# Teensy_MouseV2_0_top_Deck.net
KiCad netlist of a schematic drawn in EAGLE
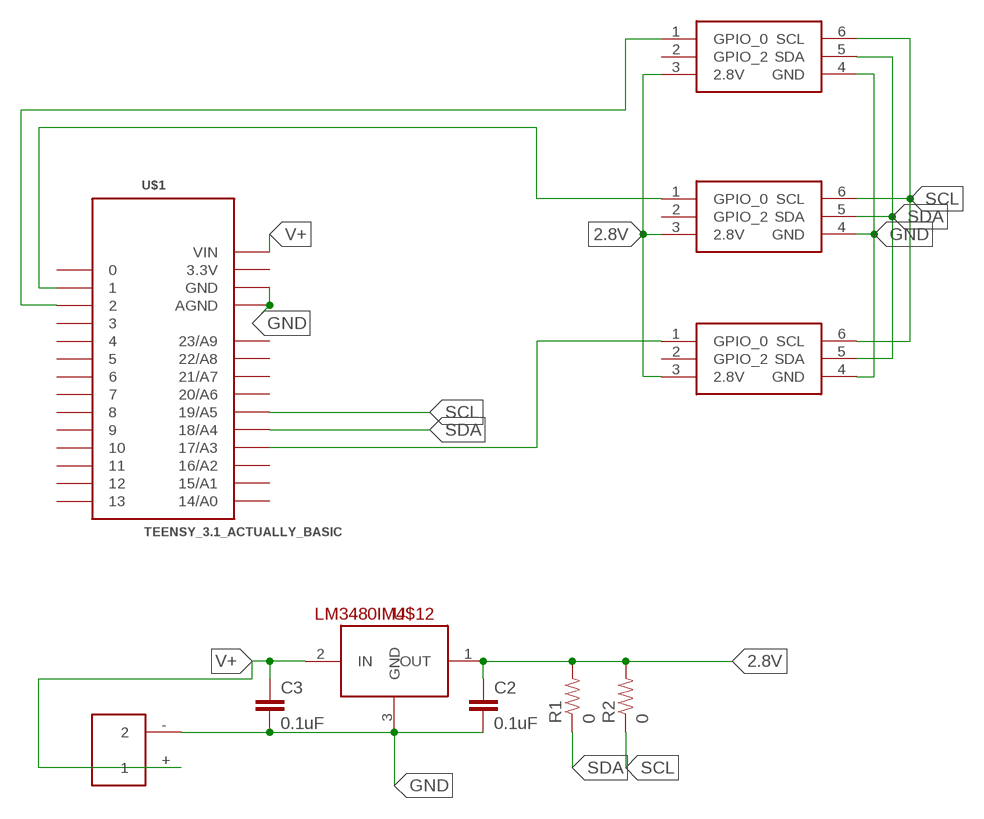
[diagram p0: schematic, sheet 1]

(export (version "E")
  (design (tool "Eeschema 10.0.6"))
  (components
    (comp (ref "C2")
      (value "0.1uF")
      (footprint "eagle-import:0603-CAP")
      (libsource (lib "eagle-import") (part "0.1UF-25V(+80/-20%)(0603)"))
    )
    (comp (ref "C3")
      (value "0.1uF")
      (footprint "eagle-import:0603-CAP")
      (libsource (lib "eagle-import") (part "0.1UF-25V(+80/-20%)(0603)"))
    )
    (comp (ref "R1")
      (value "0")
      (footprint "eagle-import:0603")
      (libsource (lib "eagle-import") (part "0OHM1/10W5%(0603)"))
    )
    (comp (ref "R2")
      (value "0")
      (footprint "eagle-import:0603")
      (libsource (lib "eagle-import") (part "0OHM1/10W5%(0603)"))
    )
    (comp (ref "U$1")
      (value "TEENSY_3.1_ACTUALLY_BASIC")
      (footprint "eagle-import:TEENSY_3.0_ACTUALLY_BASIC")
      (libsource (lib "eagle-import") (part "TEENSY_3.1_ACTUALLY_BASIC"))
    )
    (comp (ref "U$2")
      (value "PICOBLADE2X")
      (footprint "eagle-import:PICOBLADE2X")
      (libsource (lib "eagle-import") (part "PICOBLADE2X"))
    )
    (comp (ref "U$9")
      (value "PATRICK'S_ST_SENSOR_BOARD")
      (footprint "eagle-import:2X3HEADER")
      (libsource (lib "eagle-import") (part "PATRICK'S_ST_SENSOR_BOARD"))
    )
    (comp (ref "U$10")
      (value "PATRICK'S_ST_SENSOR_BOARD")
      (footprint "eagle-import:2X3HEADER")
      (libsource (lib "eagle-import") (part "PATRICK'S_ST_SENSOR_BOARD"))
    )
    (comp (ref "U$11")
      (value "PATRICK'S_ST_SENSOR_BOARD")
      (footprint "eagle-import:2X3HEADER")
      (libsource (lib "eagle-import") (part "PATRICK'S_ST_SENSOR_BOARD"))
    )
    (comp (ref "U$12")
      (value "LM3480IM4")
      (footprint "eagle-import:SOT23-3")
      (libsource (lib "eagle-import") (part "LM3480IM4"))
    )
  )
  (nets
    (net (code "1") (name "/3.3V") (class "Default")
      (node (ref "U$1") (pin "3.3V") (pinfunction "3.3V_3.3V") (pintype "power_in"))
    )
    (net (code "2") (name "2.8V") (class "Default")
      (node (ref "C2") (pin "1") (pinfunction "1_1") (pintype "passive"))
      (node (ref "R1") (pin "2") (pinfunction "2_2") (pintype "passive"))
      (node (ref "R2") (pin "2") (pinfunction "2_2") (pintype "passive"))
      (node (ref "U$10") (pin "3") (pinfunction "2.8V_3") (pintype "bidirectional"))
      (node (ref "U$11") (pin "3") (pinfunction "2.8V_3") (pintype "bidirectional"))
      (node (ref "U$12") (pin "1") (pinfunction "OUT_1") (pintype "bidirectional"))
      (node (ref "U$9") (pin "3") (pinfunction "2.8V_3") (pintype "bidirectional"))
    )
    (net (code "3") (name "GND") (class "Default")
      (node (ref "C2") (pin "2") (pinfunction "2_2") (pintype "passive"))
      (node (ref "C3") (pin "2") (pinfunction "2_2") (pintype "passive"))
      (node (ref "U$1") (pin "AGND") (pinfunction "AGND_AGND") (pintype "power_in"))
      (node (ref "U$1") (pin "GND") (pinfunction "GND_GND") (pintype "power_in"))
      (node (ref "U$10") (pin "4") (pinfunction "GND_4") (pintype "bidirectional"))
      (node (ref "U$11") (pin "4") (pinfunction "GND_4") (pintype "bidirectional"))
      (node (ref "U$12") (pin "3") (pinfunction "GND_3") (pintype "bidirectional"))
      (node (ref "U$2") (pin "-") (pinfunction "2_-") (pintype "bidirectional"))
      (node (ref "U$9") (pin "4") (pinfunction "GND_4") (pintype "bidirectional"))
    )
    (net (code "4") (name "Net-(U$9-GPIO_0)") (class "Default")
      (node (ref "U$1") (pin "2") (pinfunction "2_2") (pintype "bidirectional"))
      (node (ref "U$9") (pin "1") (pinfunction "GPIO_0_1") (pintype "bidirectional"))
    )
    (net (code "5") (name "Net-(U$10-GPIO_0)") (class "Default")
      (node (ref "U$1") (pin "1") (pinfunction "1_1") (pintype "bidirectional"))
      (node (ref "U$10") (pin "1") (pinfunction "GPIO_0_1") (pintype "bidirectional"))
    )
    (net (code "6") (name "Net-(U$11-GPIO_0)") (class "Default")
      (node (ref "U$1") (pin "17/A3") (pinfunction "17/A3_17/A3") (pintype "bidirectional"))
      (node (ref "U$11") (pin "1") (pinfunction "GPIO_0_1") (pintype "bidirectional"))
    )
    (net (code "7") (name "SCL") (class "Default")
      (node (ref "R2") (pin "1") (pinfunction "1_1") (pintype "passive"))
      (node (ref "U$1") (pin "19/A5") (pinfunction "19/A5_19/A5") (pintype "bidirectional"))
      (node (ref "U$10") (pin "6") (pinfunction "SCL_6") (pintype "bidirectional"))
      (node (ref "U$11") (pin "6") (pinfunction "SCL_6") (pintype "bidirectional"))
      (node (ref "U$9") (pin "6") (pinfunction "SCL_6") (pintype "bidirectional"))
    )
    (net (code "8") (name "SDA") (class "Default")
      (node (ref "R1") (pin "1") (pinfunction "1_1") (pintype "passive"))
      (node (ref "U$1") (pin "18/A4") (pinfunction "18/A4_18/A4") (pintype "bidirectional"))
      (node (ref "U$10") (pin "5") (pinfunction "SDA_5") (pintype "bidirectional"))
      (node (ref "U$11") (pin "5") (pinfunction "SDA_5") (pintype "bidirectional"))
      (node (ref "U$9") (pin "5") (pinfunction "SDA_5") (pintype "bidirectional"))
    )
    (net (code "9") (name "V+") (class "Default")
      (node (ref "C3") (pin "1") (pinfunction "1_1") (pintype "passive"))
      (node (ref "U$1") (pin "VIN") (pinfunction "VIN_VIN") (pintype "power_in"))
      (node (ref "U$12") (pin "2") (pinfunction "IN_2") (pintype "bidirectional"))
      (node (ref "U$2") (pin "+") (pinfunction "1_+") (pintype "bidirectional"))
    )
    (net (code "10") (name "unconnected-(U$1-Pad0)") (class "Default")
      (node (ref "U$1") (pin "0") (pinfunction "0_0") (pintype "bidirectional"))
    )
    (net (code "11") (name "unconnected-(U$1-Pad3)") (class "Default")
      (node (ref "U$1") (pin "3") (pinfunction "3_3") (pintype "bidirectional"))
    )
    (net (code "12") (name "unconnected-(U$1-Pad4)") (class "Default")
      (node (ref "U$1") (pin "4") (pinfunction "4_4") (pintype "bidirectional"))
    )
    (net (code "13") (name "unconnected-(U$1-Pad5)") (class "Default")
      (node (ref "U$1") (pin "5") (pinfunction "5_5") (pintype "bidirectional"))
    )
    (net (code "14") (name "unconnected-(U$1-Pad6)") (class "Default")
      (node (ref "U$1") (pin "6") (pinfunction "6_6") (pintype "bidirectional"))
    )
    (net (code "15") (name "unconnected-(U$1-Pad7)") (class "Default")
      (node (ref "U$1") (pin "7") (pinfunction "7_7") (pintype "bidirectional"))
    )
    (net (code "16") (name "unconnected-(U$1-Pad8)") (class "Default")
      (node (ref "U$1") (pin "8") (pinfunction "8_8") (pintype "bidirectional"))
    )
    (net (code "17") (name "unconnected-(U$1-Pad9)") (class "Default")
      (node (ref "U$1") (pin "9") (pinfunction "9_9") (pintype "bidirectional"))
    )
    (net (code "18") (name "unconnected-(U$1-Pad10)") (class "Default")
      (node (ref "U$1") (pin "10") (pinfunction "10_10") (pintype "bidirectional"))
    )
    (net (code "19") (name "unconnected-(U$1-Pad11)") (class "Default")
      (node (ref "U$1") (pin "11") (pinfunction "11_11") (pintype "bidirectional"))
    )
    (net (code "20") (name "unconnected-(U$1-Pad12)") (class "Default")
      (node (ref "U$1") (pin "12") (pinfunction "12_12") (pintype "bidirectional"))
    )
    (net (code "21") (name "unconnected-(U$1-Pad13)") (class "Default")
      (node (ref "U$1") (pin "13") (pinfunction "13_13") (pintype "bidirectional"))
    )
    (net (code "22") (name "unconnected-(U$1-Pad14{slash}A0)") (class "Default")
      (node (ref "U$1") (pin "14/A0") (pinfunction "14/A0_14/A0") (pintype "bidirectional"))
    )
    (net (code "23") (name "unconnected-(U$1-Pad15{slash}A1)") (class "Default")
      (node (ref "U$1") (pin "15/A1") (pinfunction "15/A1_15/A1") (pintype "bidirectional"))
    )
    (net (code "24") (name "unconnected-(U$1-Pad16{slash}A2)") (class "Default")
      (node (ref "U$1") (pin "16/A2") (pinfunction "16/A2_16/A2") (pintype "bidirectional"))
    )
    (net (code "25") (name "unconnected-(U$1-Pad20{slash}A6)") (class "Default")
      (node (ref "U$1") (pin "20/A6") (pinfunction "20/A6_20/A6") (pintype "bidirectional"))
    )
    (net (code "26") (name "unconnected-(U$1-Pad21{slash}A7)") (class "Default")
      (node (ref "U$1") (pin "21/A7") (pinfunction "21/A7_21/A7") (pintype "bidirectional"))
    )
    (net (code "27") (name "unconnected-(U$1-Pad22{slash}A8)") (class "Default")
      (node (ref "U$1") (pin "22/A8") (pinfunction "22/A8_22/A8") (pintype "bidirectional"))
    )
    (net (code "28") (name "unconnected-(U$1-Pad23{slash}A9)") (class "Default")
      (node (ref "U$1") (pin "23/A9") (pinfunction "23/A9_23/A9") (pintype "bidirectional"))
    )
    (net (code "29") (name "unconnected-(U$9-GPIO_2-Pad2)") (class "Default")
      (node (ref "U$9") (pin "2") (pinfunction "GPIO_2_2") (pintype "bidirectional"))
    )
    (net (code "30") (name "unconnected-(U$10-GPIO_2-Pad2)") (class "Default")
      (node (ref "U$10") (pin "2") (pinfunction "GPIO_2_2") (pintype "bidirectional"))
    )
    (net (code "31") (name "unconnected-(U$11-GPIO_2-Pad2)") (class "Default")
      (node (ref "U$11") (pin "2") (pinfunction "GPIO_2_2") (pintype "bidirectional"))
    )
  )
)
